# Speed.net
KiCad netlist of a schematic drawn in EAGLE
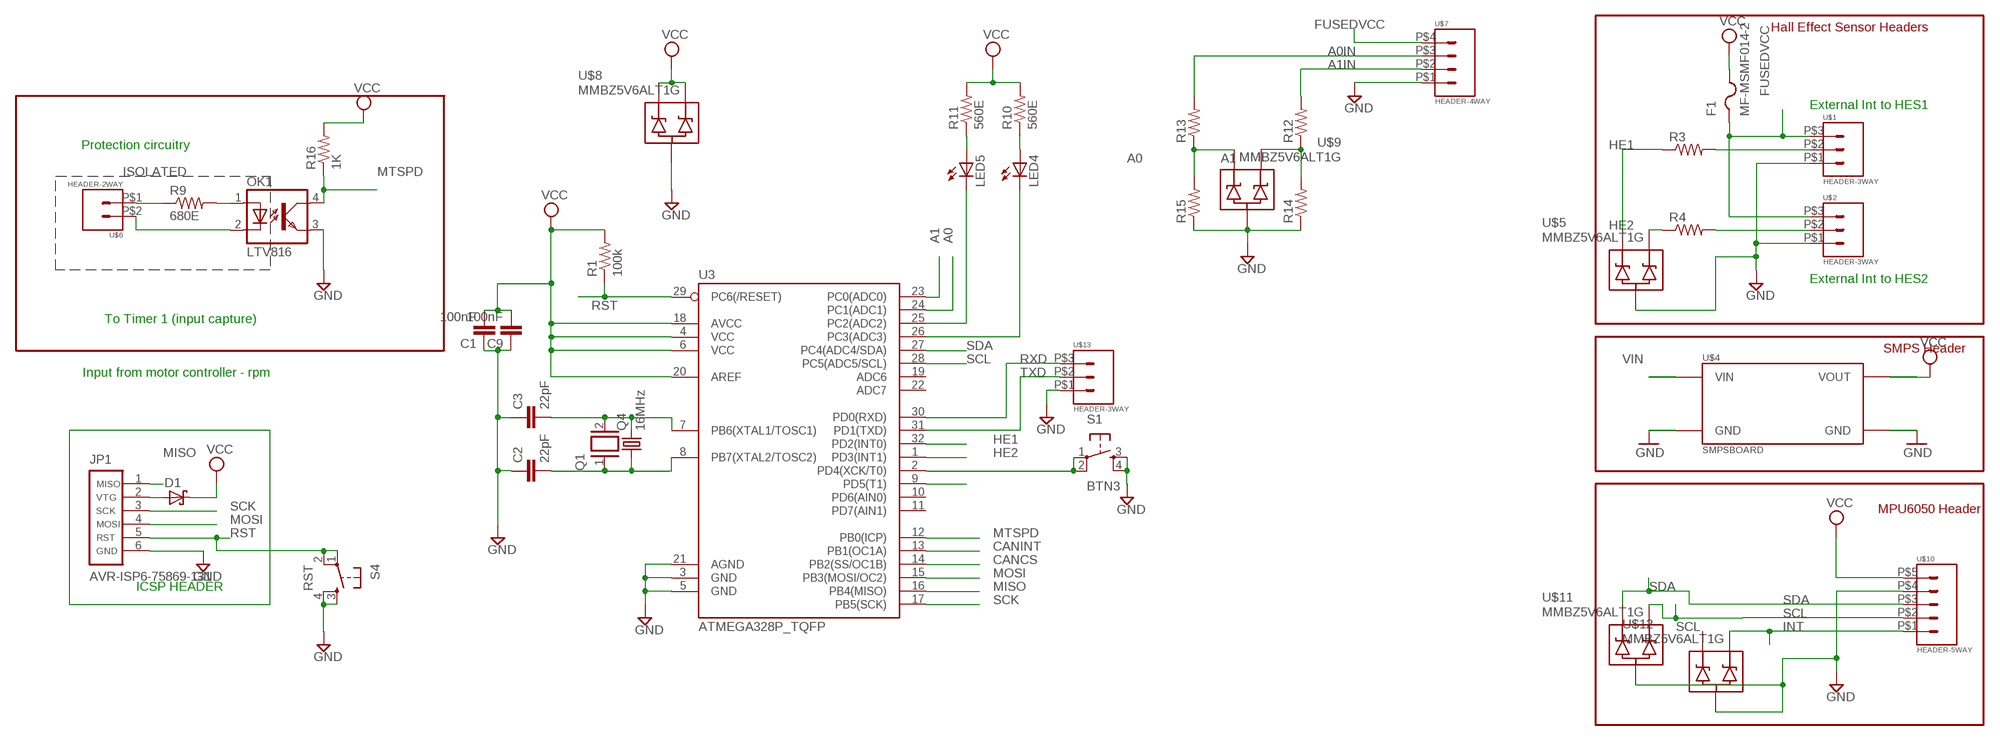
[diagram p0: schematic, sheet 1]
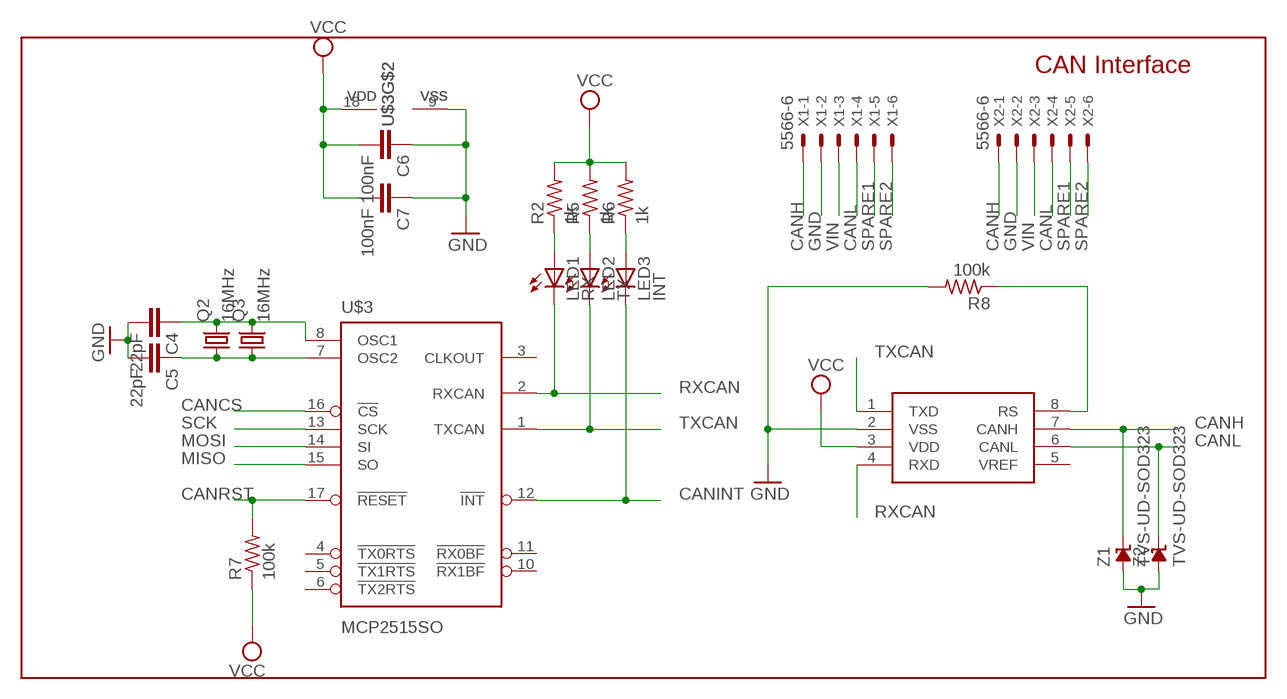
[diagram p1: schematic, sheet 2]

(export (version "E")
  (design (tool "Eeschema 10.0.6"))
  (components
    (comp (ref "C4")
      (value "22pF")
      (footprint "eagle-import:C0805K")
      (libsource (lib "eagle-import") (part "C-EUC0805K"))
    )
    (comp (ref "C5")
      (value "22pF")
      (footprint "eagle-import:C0805K")
      (libsource (lib "eagle-import") (part "C-EUC0805K"))
    )
    (comp (ref "C6")
      (value "100nF")
      (footprint "eagle-import:C0805K")
      (libsource (lib "eagle-import") (part "C-EUC0805K"))
    )
    (comp (ref "C7")
      (value "100nF")
      (footprint "eagle-import:C0805K")
      (libsource (lib "eagle-import") (part "C-EUC0805K"))
    )
    (comp (ref "LED1")
      (value "RX")
      (footprint "eagle-import:CHIP-LED0805")
      (libsource (lib "eagle-import") (part "LEDCHIP-LED0805"))
    )
    (comp (ref "LED2")
      (value "TX")
      (footprint "eagle-import:CHIP-LED0805")
      (libsource (lib "eagle-import") (part "LEDCHIP-LED0805"))
    )
    (comp (ref "LED3")
      (value "INT")
      (footprint "eagle-import:CHIP-LED0805")
      (libsource (lib "eagle-import") (part "LEDCHIP-LED0805"))
    )
    (comp (ref "Q2")
      (value "16MHz")
      (footprint "eagle-import:HC49_S")
      (libsource (lib "eagle-import") (part "CRYSTALHC49S"))
    )
    (comp (ref "Q3")
      (value "16MHz")
      (footprint "eagle-import:HC49UP")
      (libsource (lib "eagle-import") (part "CRYSTALHC49UP"))
    )
    (comp (ref "R2")
      (value "1k")
      (footprint "eagle-import:R0805")
      (libsource (lib "eagle-import") (part "R-US_R0805"))
    )
    (comp (ref "R5")
      (value "1k")
      (footprint "eagle-import:R0805")
      (libsource (lib "eagle-import") (part "R-US_R0805"))
    )
    (comp (ref "R6")
      (value "1k")
      (footprint "eagle-import:R0805")
      (libsource (lib "eagle-import") (part "R-US_R0805"))
    )
    (comp (ref "R7")
      (value "100k")
      (footprint "eagle-import:R0805")
      (libsource (lib "eagle-import") (part "R-US_R0805"))
    )
    (comp (ref "R8")
      (value "100k")
      (footprint "eagle-import:R0805")
      (libsource (lib "eagle-import") (part "R-US_R0805"))
    )
    (comp (ref "U$3")
      (value "MCP2515SO")
      (footprint "eagle-import:SO-18W")
      (libsource (lib "eagle-import") (part "MCP2515SO"))
    )
    (comp (ref "U2")
      (value "MCP2551")
      (footprint "eagle-import:SO08")
      (libsource (lib "eagle-import") (part "MCP2551"))
    )
    (comp (ref "X1")
      (value "5566-6")
      (footprint "eagle-import:5566-6")
      (fields (field (name "MPN") "95566-61002"))
      (libsource (lib "eagle-import") (part "5566-6"))
    )
    (comp (ref "X2")
      (value "5566-6")
      (footprint "eagle-import:5566-6")
      (fields (field (name "MPN") "95566-61002"))
      (libsource (lib "eagle-import") (part "5566-6"))
    )
    (comp (ref "Z1")
      (value "TVS-UD-SOD323")
      (footprint "eagle-import:SOD323")
      (libsource (lib "eagle-import") (part "TVS-UD-SOD323"))
    )
    (comp (ref "Z2")
      (value "TVS-UD-SOD323")
      (footprint "eagle-import:SOD323")
      (libsource (lib "eagle-import") (part "TVS-UD-SOD323"))
    )
    (comp (ref "C1")
      (value "100nF")
      (footprint "eagle-import:C0805")
      (libsource (lib "eagle-import") (part "C-EUC0805"))
    )
    (comp (ref "C2")
      (value "22pF")
      (footprint "eagle-import:C0805")
      (libsource (lib "eagle-import") (part "C-EUC0805"))
    )
    (comp (ref "C3")
      (value "22pF")
      (footprint "eagle-import:C0805")
      (libsource (lib "eagle-import") (part "C-EUC0805"))
    )
    (comp (ref "C9")
      (value "100nF")
      (footprint "eagle-import:C0805")
      (libsource (lib "eagle-import") (part "C-EUC0805"))
    )
    (comp (ref "D1")
      (value "SCHOTTKY-DIODESMD")
      (footprint "eagle-import:SMB")
      (libsource (lib "eagle-import") (part "SCHOTTKY-DIODESMD"))
    )
    (comp (ref "F1")
      (value "MF-MSMF014-2")
      (footprint "eagle-import:1812")
      (libsource (lib "eagle-import") (part "PTCFUSE-1812"))
    )
    (comp (ref "JP1")
      (value "AVR-ISP6-75869-131")
      (footprint "eagle-import:HDR-75869-131")
      (libsource (lib "eagle-import") (part "AVR-ISP6-75869-131"))
    )
    (comp (ref "LED4")
      (value "LEDCHIP-LED0805")
      (footprint "eagle-import:CHIP-LED0805")
      (libsource (lib "eagle-import") (part "LEDCHIP-LED0805"))
    )
    (comp (ref "LED5")
      (value "LEDCHIP-LED0805")
      (footprint "eagle-import:CHIP-LED0805")
      (libsource (lib "eagle-import") (part "LEDCHIP-LED0805"))
    )
    (comp (ref "OK1")
      (value "LTV816")
      (footprint "eagle-import:DIL04")
      (libsource (lib "eagle-import") (part "LTV816"))
    )
    (comp (ref "Q1")
      (value "XTAL/S")
      (footprint "eagle-import:QS")
      (libsource (lib "eagle-import") (part "XTAL/S"))
    )
    (comp (ref "Q4")
      (value "16MHz")
      (footprint "eagle-import:HC49UP")
      (libsource (lib "eagle-import") (part "CRYSTALHC49UP"))
    )
    (comp (ref "R1")
      (value "100k")
      (footprint "eagle-import:M0805")
      (libsource (lib "eagle-import") (part "R-US_M0805"))
    )
    (comp (ref "R3")
      (value "R-US_M0805")
      (footprint "eagle-import:M0805")
      (libsource (lib "eagle-import") (part "R-US_M0805"))
    )
    (comp (ref "R4")
      (value "R-US_M0805")
      (footprint "eagle-import:M0805")
      (libsource (lib "eagle-import") (part "R-US_M0805"))
    )
    (comp (ref "R9")
      (value "680E")
      (footprint "eagle-import:M0805")
      (libsource (lib "eagle-import") (part "R-US_M0805"))
    )
    (comp (ref "R10")
      (value "560E")
      (footprint "eagle-import:M0805")
      (libsource (lib "eagle-import") (part "R-US_M0805"))
    )
    (comp (ref "R11")
      (value "560E")
      (footprint "eagle-import:M0805")
      (libsource (lib "eagle-import") (part "R-US_M0805"))
    )
    (comp (ref "R12")
      (value "R-US_M0805")
      (footprint "eagle-import:M0805")
      (libsource (lib "eagle-import") (part "R-US_M0805"))
    )
    (comp (ref "R13")
      (value "R-US_M0805")
      (footprint "eagle-import:M0805")
      (libsource (lib "eagle-import") (part "R-US_M0805"))
    )
    (comp (ref "R14")
      (value "R-US_M0805")
      (footprint "eagle-import:M0805")
      (libsource (lib "eagle-import") (part "R-US_M0805"))
    )
    (comp (ref "R15")
      (value "R-US_M0805")
      (footprint "eagle-import:M0805")
      (libsource (lib "eagle-import") (part "R-US_M0805"))
    )
    (comp (ref "R16")
      (value "1K")
      (footprint "eagle-import:M0805")
      (libsource (lib "eagle-import") (part "R-US_M0805"))
    )
    (comp (ref "S1")
      (value "BTN3")
      (footprint "eagle-import:TACTILE_SWITCH_SMD")
      (libsource (lib "eagle-import") (part "TAC_SWITCHSMD"))
    )
    (comp (ref "S4")
      (value "RST")
      (footprint "eagle-import:TACTILE_SWITCH_SMD")
      (libsource (lib "eagle-import") (part "TAC_SWITCHSMD"))
    )
    (comp (ref "U$1")
      (value "HEADER-3WAY")
      (footprint "eagle-import:1744426-3")
      (libsource (lib "eagle-import") (part "HEADER-3WAY"))
    )
    (comp (ref "U$2")
      (value "HEADER-3WAY")
      (footprint "eagle-import:1744426-3")
      (libsource (lib "eagle-import") (part "HEADER-3WAY"))
    )
    (comp (ref "U$4")
      (value "SMPSBOARD")
      (footprint "eagle-import:SMPSBOARD")
      (libsource (lib "eagle-import") (part "SMPSBOARD"))
    )
    (comp (ref "U$5")
      (value "MMBZ5V6ALT1G")
      (footprint "eagle-import:SOT23")
      (libsource (lib "eagle-import") (part "MMBZ5V6ALT1G"))
    )
    (comp (ref "U$6")
      (value "HEADER-2WAY")
      (footprint "eagle-import:1744426-2")
      (libsource (lib "eagle-import") (part "HEADER-2WAY"))
    )
    (comp (ref "U$7")
      (value "HEADER-4WAY")
      (footprint "eagle-import:1744426-4")
      (libsource (lib "eagle-import") (part "HEADER-4WAY"))
    )
    (comp (ref "U$8")
      (value "MMBZ5V6ALT1G")
      (footprint "eagle-import:SOT23")
      (libsource (lib "eagle-import") (part "MMBZ5V6ALT1G"))
    )
    (comp (ref "U$9")
      (value "MMBZ5V6ALT1G")
      (footprint "eagle-import:SOT23")
      (libsource (lib "eagle-import") (part "MMBZ5V6ALT1G"))
    )
    (comp (ref "U$10")
      (value "HEADER-5WAY")
      (footprint "eagle-import:1744426-5")
      (libsource (lib "eagle-import") (part "HEADER-5WAY"))
    )
    (comp (ref "U$11")
      (value "MMBZ5V6ALT1G")
      (footprint "eagle-import:SOT23")
      (libsource (lib "eagle-import") (part "MMBZ5V6ALT1G"))
    )
    (comp (ref "U$12")
      (value "MMBZ5V6ALT1G")
      (footprint "eagle-import:SOT23")
      (libsource (lib "eagle-import") (part "MMBZ5V6ALT1G"))
    )
    (comp (ref "U$13")
      (value "HEADER-3WAY")
      (footprint "eagle-import:1744426-3")
      (libsource (lib "eagle-import") (part "HEADER-3WAY"))
    )
    (comp (ref "U3")
      (value "ATMEGA328P_TQFP")
      (footprint "eagle-import:TQFP32-08")
      (libsource (lib "eagle-import") (part "ATMEGA328P_TQFP"))
    )
  )
  (nets
    (net (code "1") (name "A0") (class "Default")
      (node (ref "R12") (pin "1") (pinfunction "1_1") (pintype "passive"))
      (node (ref "R14") (pin "2") (pinfunction "2_2") (pintype "passive"))
      (node (ref "U$9") (pin "2") (pinfunction "A2_2") (pintype "passive"))
      (node (ref "U3") (pin "24") (pinfunction "PC1(ADC1)_24") (pintype "bidirectional"))
    )
    (net (code "2") (name "A0IN") (class "Default")
      (node (ref "R13") (pin "2") (pinfunction "2_2") (pintype "passive"))
      (node (ref "U$7") (pin "P$3") (pinfunction "P$3_P$3") (pintype "passive"))
    )
    (net (code "3") (name "A1") (class "Default")
      (node (ref "R13") (pin "1") (pinfunction "1_1") (pintype "passive"))
      (node (ref "R15") (pin "2") (pinfunction "2_2") (pintype "passive"))
      (node (ref "U$9") (pin "1") (pinfunction "A1_1") (pintype "passive"))
      (node (ref "U3") (pin "23") (pinfunction "PC0(ADC0)_23") (pintype "bidirectional"))
    )
    (net (code "4") (name "A1IN") (class "Default")
      (node (ref "R12") (pin "2") (pinfunction "2_2") (pintype "passive"))
      (node (ref "U$7") (pin "P$2") (pinfunction "P$2_P$2") (pintype "passive"))
    )
    (net (code "5") (name "CANCS") (class "Default")
      (node (ref "U$3") (pin "16") (pinfunction "~{CS}_16") (pintype "input"))
      (node (ref "U3") (pin "14") (pinfunction "PB2(SS/OC1B)_14") (pintype "bidirectional"))
    )
    (net (code "6") (name "CANH") (class "Default")
      (node (ref "U2") (pin "7") (pinfunction "CANH_7") (pintype "bidirectional"))
      (node (ref "X1") (pin "1") (pinfunction "S_1") (pintype "passive"))
      (node (ref "X2") (pin "1") (pinfunction "S_1") (pintype "passive"))
      (node (ref "Z1") (pin "C") (pinfunction "C_C") (pintype "passive"))
    )
    (net (code "7") (name "CANINT") (class "Default")
      (node (ref "LED3") (pin "C") (pinfunction "C_C") (pintype "passive"))
      (node (ref "U$3") (pin "12") (pinfunction "~{INT}_12") (pintype "output"))
      (node (ref "U3") (pin "13") (pinfunction "PB1(OC1A)_13") (pintype "bidirectional"))
    )
    (net (code "8") (name "CANL") (class "Default")
      (node (ref "U2") (pin "6") (pinfunction "CANL_6") (pintype "bidirectional"))
      (node (ref "X1") (pin "4") (pinfunction "S_4") (pintype "passive"))
      (node (ref "X2") (pin "4") (pinfunction "S_4") (pintype "passive"))
      (node (ref "Z2") (pin "C") (pinfunction "C_C") (pintype "passive"))
    )
    (net (code "9") (name "CANRST") (class "Default")
      (node (ref "R7") (pin "2") (pinfunction "2_2") (pintype "passive"))
      (node (ref "U$3") (pin "17") (pinfunction "~{RESET}_17") (pintype "input"))
    )
    (net (code "10") (name "FUSEDVCC") (class "Default")
      (node (ref "F1") (pin "1") (pinfunction "1_1") (pintype "passive"))
      (node (ref "U$1") (pin "P$3") (pinfunction "P$3_P$3") (pintype "passive"))
      (node (ref "U$2") (pin "P$3") (pinfunction "P$3_P$3") (pintype "passive"))
      (node (ref "U$7") (pin "P$4") (pinfunction "P$4_P$4") (pintype "passive"))
    )
    (net (code "11") (name "GND") (class "Default")
      (node (ref "C1") (pin "1") (pinfunction "1_1") (pintype "passive"))
      (node (ref "C2") (pin "1") (pinfunction "1_1") (pintype "passive"))
      (node (ref "C3") (pin "1") (pinfunction "1_1") (pintype "passive"))
      (node (ref "C4") (pin "2") (pinfunction "2_2") (pintype "passive"))
      (node (ref "C5") (pin "2") (pinfunction "2_2") (pintype "passive"))
      (node (ref "C6") (pin "1") (pinfunction "1_1") (pintype "passive"))
      (node (ref "C7") (pin "1") (pinfunction "1_1") (pintype "passive"))
      (node (ref "C9") (pin "1") (pinfunction "1_1") (pintype "passive"))
      (node (ref "JP1") (pin "6") (pinfunction "6_6") (pintype "passive"))
      (node (ref "OK1") (pin "3") (pinfunction "EMIT_3") (pintype "passive"))
      (node (ref "R14") (pin "1") (pinfunction "1_1") (pintype "passive"))
      (node (ref "R15") (pin "1") (pinfunction "1_1") (pintype "passive"))
      (node (ref "R8") (pin "2") (pinfunction "2_2") (pintype "passive"))
      (node (ref "S1") (pin "3") (pinfunction "3_3") (pintype "passive"))
      (node (ref "S1") (pin "4") (pinfunction "4_4") (pintype "passive"))
      (node (ref "S4") (pin "3") (pinfunction "3_3") (pintype "passive"))
      (node (ref "S4") (pin "4") (pinfunction "4_4") (pintype "passive"))
      (node (ref "U$1") (pin "P$1") (pinfunction "P$1_P$1") (pintype "passive"))
      (node (ref "U$10") (pin "P$4") (pinfunction "P$4_P$4") (pintype "passive"))
      (node (ref "U$11") (pin "3") (pinfunction "C_3") (pintype "passive"))
      (node (ref "U$12") (pin "3") (pinfunction "C_3") (pintype "passive"))
      (node (ref "U$13") (pin "P$1") (pinfunction "P$1_P$1") (pintype "passive"))
      (node (ref "U$2") (pin "P$1") (pinfunction "P$1_P$1") (pintype "passive"))
      (node (ref "U$3") (pin "9") (pinfunction "VSS_9") (pintype "power_in"))
      (node (ref "U$4") (pin "GND") (pinfunction "GND_GND") (pintype "bidirectional"))
      (node (ref "U$4") (pin "GND@") (pinfunction "GND_GND@") (pintype "bidirectional"))
      (node (ref "U$5") (pin "3") (pinfunction "C_3") (pintype "passive"))
      (node (ref "U$7") (pin "P$1") (pinfunction "P$1_P$1") (pintype "passive"))
      (node (ref "U$8") (pin "3") (pinfunction "C_3") (pintype "passive"))
      (node (ref "U$9") (pin "3") (pinfunction "C_3") (pintype "passive"))
      (node (ref "U2") (pin "2") (pinfunction "VSS_2") (pintype "bidirectional"))
      (node (ref "U3") (pin "21") (pinfunction "AGND_21") (pintype "bidirectional"))
      (node (ref "U3") (pin "3") (pinfunction "GND_3") (pintype "bidirectional"))
      (node (ref "U3") (pin "5") (pinfunction "GND_5") (pintype "bidirectional"))
      (node (ref "X1") (pin "2") (pinfunction "S_2") (pintype "passive"))
      (node (ref "X2") (pin "2") (pinfunction "S_2") (pintype "passive"))
      (node (ref "Z1") (pin "A") (pinfunction "A_A") (pintype "passive"))
      (node (ref "Z2") (pin "A") (pinfunction "A_A") (pintype "passive"))
    )
    (net (code "12") (name "HE1") (class "Default")
      (node (ref "R3") (pin "1") (pinfunction "1_1") (pintype "passive"))
      (node (ref "U$5") (pin "2") (pinfunction "A2_2") (pintype "passive"))
      (node (ref "U3") (pin "32") (pinfunction "PD2(INT0)_32") (pintype "bidirectional"))
    )
    (net (code "13") (name "HE2") (class "Default")
      (node (ref "R4") (pin "1") (pinfunction "1_1") (pintype "passive"))
      (node (ref "U$5") (pin "1") (pinfunction "A1_1") (pintype "passive"))
      (node (ref "U3") (pin "1") (pinfunction "PD3(INT1)_1") (pintype "bidirectional"))
    )
    (net (code "14") (name "INT") (class "Default")
      (node (ref "U$10") (pin "P$1") (pinfunction "P$1_P$1") (pintype "passive"))
      (node (ref "U$12") (pin "1") (pinfunction "A1_1") (pintype "passive"))
      (node (ref "U3") (pin "9") (pinfunction "PD5(T1)_9") (pintype "bidirectional"))
    )
    (net (code "15") (name "MISO") (class "Default")
      (node (ref "JP1") (pin "1") (pinfunction "1_1") (pintype "passive"))
      (node (ref "U$3") (pin "15") (pinfunction "SO_15") (pintype "output"))
      (node (ref "U3") (pin "16") (pinfunction "PB4(MISO)_16") (pintype "bidirectional"))
    )
    (net (code "16") (name "MOSI") (class "Default")
      (node (ref "JP1") (pin "4") (pinfunction "4_4") (pintype "passive"))
      (node (ref "U$3") (pin "14") (pinfunction "SI_14") (pintype "input"))
      (node (ref "U3") (pin "15") (pinfunction "PB3(MOSI/OC2)_15") (pintype "bidirectional"))
    )
    (net (code "17") (name "MTSPD") (class "Default")
      (node (ref "OK1") (pin "4") (pinfunction "COL_4") (pintype "passive"))
      (node (ref "R16") (pin "1") (pinfunction "1_1") (pintype "passive"))
      (node (ref "U3") (pin "12") (pinfunction "PB0(ICP)_12") (pintype "bidirectional"))
    )
    (net (code "18") (name "Net-(D1-PadA)") (class "Default")
      (node (ref "D1") (pin "A") (pinfunction "A_A") (pintype "passive"))
      (node (ref "JP1") (pin "2") (pinfunction "2_2") (pintype "passive"))
    )
    (net (code "19") (name "Net-(LED1-PadA)") (class "Default")
      (node (ref "LED1") (pin "A") (pinfunction "A_A") (pintype "passive"))
      (node (ref "R2") (pin "1") (pinfunction "1_1") (pintype "passive"))
    )
    (net (code "20") (name "Net-(LED2-PadA)") (class "Default")
      (node (ref "LED2") (pin "A") (pinfunction "A_A") (pintype "passive"))
      (node (ref "R5") (pin "1") (pinfunction "1_1") (pintype "passive"))
    )
    (net (code "21") (name "Net-(LED3-PadA)") (class "Default")
      (node (ref "LED3") (pin "A") (pinfunction "A_A") (pintype "passive"))
      (node (ref "R6") (pin "1") (pinfunction "1_1") (pintype "passive"))
    )
    (net (code "22") (name "Net-(LED4-PadA)") (class "Default")
      (node (ref "LED4") (pin "A") (pinfunction "A_A") (pintype "passive"))
      (node (ref "R10") (pin "1") (pinfunction "1_1") (pintype "passive"))
    )
    (net (code "23") (name "Net-(LED5-PadA)") (class "Default")
      (node (ref "LED5") (pin "A") (pinfunction "A_A") (pintype "passive"))
      (node (ref "R11") (pin "1") (pinfunction "1_1") (pintype "passive"))
    )
    (net (code "24") (name "Net-(OK1-A)") (class "Default")
      (node (ref "OK1") (pin "1") (pinfunction "A_1") (pintype "passive"))
      (node (ref "R9") (pin "2") (pinfunction "2_2") (pintype "passive"))
    )
    (net (code "25") (name "Net-(OK1-C)") (class "Default")
      (node (ref "OK1") (pin "2") (pinfunction "C_2") (pintype "passive"))
      (node (ref "U$6") (pin "P$2") (pinfunction "P$2_P$2") (pintype "passive"))
    )
    (net (code "26") (name "Net-(R3-Pad2)") (class "Default")
      (node (ref "R3") (pin "2") (pinfunction "2_2") (pintype "passive"))
      (node (ref "U$1") (pin "P$2") (pinfunction "P$2_P$2") (pintype "passive"))
    )
    (net (code "27") (name "Net-(R4-Pad2)") (class "Default")
      (node (ref "R4") (pin "2") (pinfunction "2_2") (pintype "passive"))
      (node (ref "U$2") (pin "P$2") (pinfunction "P$2_P$2") (pintype "passive"))
    )
    (net (code "28") (name "Net-(R9-Pad1)") (class "Default")
      (node (ref "R9") (pin "1") (pinfunction "1_1") (pintype "passive"))
      (node (ref "U$6") (pin "P$1") (pinfunction "P$1_P$1") (pintype "passive"))
    )
    (net (code "29") (name "Net-(U$3A-OSC1)") (class "Default")
      (node (ref "C4") (pin "1") (pinfunction "1_1") (pintype "passive"))
      (node (ref "Q2") (pin "2") (pinfunction "2_2") (pintype "passive"))
      (node (ref "Q3") (pin "2") (pinfunction "2_2") (pintype "passive"))
      (node (ref "U$3") (pin "8") (pinfunction "OSC1_8") (pintype "input"))
    )
    (net (code "30") (name "Net-(U$3A-OSC2)") (class "Default")
      (node (ref "C5") (pin "1") (pinfunction "1_1") (pintype "passive"))
      (node (ref "Q2") (pin "1") (pinfunction "1_1") (pintype "passive"))
      (node (ref "Q3") (pin "1") (pinfunction "1_1") (pintype "passive"))
      (node (ref "U$3") (pin "7") (pinfunction "OSC2_7") (pintype "output"))
    )
    (net (code "31") (name "Net-(U2-RS)") (class "Default")
      (node (ref "R8") (pin "1") (pinfunction "1_1") (pintype "passive"))
      (node (ref "U2") (pin "8") (pinfunction "RS_8") (pintype "bidirectional"))
    )
    (net (code "32") (name "Net-(U3-PB6(XTAL1{slash}TOSC1))") (class "Default")
      (node (ref "C3") (pin "2") (pinfunction "2_2") (pintype "passive"))
      (node (ref "Q1") (pin "2") (pinfunction "2_2") (pintype "passive"))
      (node (ref "Q4") (pin "2") (pinfunction "2_2") (pintype "passive"))
      (node (ref "U3") (pin "7") (pinfunction "PB6(XTAL1/TOSC1)_7") (pintype "bidirectional"))
    )
    (net (code "33") (name "Net-(U3-PB7(XTAL2{slash}TOSC2))") (class "Default")
      (node (ref "C2") (pin "2") (pinfunction "2_2") (pintype "passive"))
      (node (ref "Q1") (pin "1") (pinfunction "1_1") (pintype "passive"))
      (node (ref "Q4") (pin "1") (pinfunction "1_1") (pintype "passive"))
      (node (ref "U3") (pin "8") (pinfunction "PB7(XTAL2/TOSC2)_8") (pintype "bidirectional"))
    )
    (net (code "34") (name "Net-(U3-PC2(ADC2))") (class "Default")
      (node (ref "LED5") (pin "C") (pinfunction "C_C") (pintype "passive"))
      (node (ref "U3") (pin "25") (pinfunction "PC2(ADC2)_25") (pintype "bidirectional"))
    )
    (net (code "35") (name "Net-(U3-PC3(ADC3))") (class "Default")
      (node (ref "LED4") (pin "C") (pinfunction "C_C") (pintype "passive"))
      (node (ref "U3") (pin "26") (pinfunction "PC3(ADC3)_26") (pintype "bidirectional"))
    )
    (net (code "36") (name "Net-(U3-PD4(XCK{slash}T0))") (class "Default")
      (node (ref "S1") (pin "1") (pinfunction "1_1") (pintype "passive"))
      (node (ref "S1") (pin "2") (pinfunction "2_2") (pintype "passive"))
      (node (ref "U3") (pin "2") (pinfunction "PD4(XCK/T0)_2") (pintype "bidirectional"))
    )
    (net (code "37") (name "RST") (class "Default")
      (node (ref "JP1") (pin "5") (pinfunction "5_5") (pintype "passive"))
      (node (ref "R1") (pin "1") (pinfunction "1_1") (pintype "passive"))
      (node (ref "S4") (pin "1") (pinfunction "1_1") (pintype "passive"))
      (node (ref "S4") (pin "2") (pinfunction "2_2") (pintype "passive"))
      (node (ref "U3") (pin "29") (pinfunction "PC6(/RESET)_29") (pintype "bidirectional"))
    )
    (net (code "38") (name "RXCAN") (class "Default")
      (node (ref "LED1") (pin "C") (pinfunction "C_C") (pintype "passive"))
      (node (ref "U$3") (pin "2") (pinfunction "RXCAN_2") (pintype "input"))
      (node (ref "U2") (pin "4") (pinfunction "RXD_4") (pintype "bidirectional"))
    )
    (net (code "39") (name "RXD") (class "Default")
      (node (ref "U$13") (pin "P$3") (pinfunction "P$3_P$3") (pintype "passive"))
      (node (ref "U3") (pin "30") (pinfunction "PD0(RXD)_30") (pintype "bidirectional"))
    )
    (net (code "40") (name "SCK") (class "Default")
      (node (ref "JP1") (pin "3") (pinfunction "3_3") (pintype "passive"))
      (node (ref "U$3") (pin "13") (pinfunction "SCK_13") (pintype "input"))
      (node (ref "U3") (pin "17") (pinfunction "PB5(SCK)_17") (pintype "bidirectional"))
    )
    (net (code "41") (name "SCL") (class "Default")
      (node (ref "U$10") (pin "P$2") (pinfunction "P$2_P$2") (pintype "passive"))
      (node (ref "U$11") (pin "1") (pinfunction "A1_1") (pintype "passive"))
      (node (ref "U3") (pin "28") (pinfunction "PC5(ADC5/SCL)_28") (pintype "bidirectional"))
    )
    (net (code "42") (name "SDA") (class "Default")
      (node (ref "U$10") (pin "P$3") (pinfunction "P$3_P$3") (pintype "passive"))
      (node (ref "U$11") (pin "2") (pinfunction "A2_2") (pintype "passive"))
      (node (ref "U3") (pin "27") (pinfunction "PC4(ADC4/SDA)_27") (pintype "bidirectional"))
    )
    (net (code "43") (name "SPARE1") (class "Default")
      (node (ref "X1") (pin "5") (pinfunction "S_5") (pintype "passive"))
      (node (ref "X2") (pin "5") (pinfunction "S_5") (pintype "passive"))
    )
    (net (code "44") (name "SPARE2") (class "Default")
      (node (ref "X1") (pin "6") (pinfunction "S_6") (pintype "passive"))
      (node (ref "X2") (pin "6") (pinfunction "S_6") (pintype "passive"))
    )
    (net (code "45") (name "TXCAN") (class "Default")
      (node (ref "LED2") (pin "C") (pinfunction "C_C") (pintype "passive"))
      (node (ref "U$3") (pin "1") (pinfunction "TXCAN_1") (pintype "output"))
      (node (ref "U2") (pin "1") (pinfunction "TXD_1") (pintype "bidirectional"))
    )
    (net (code "46") (name "TXD") (class "Default")
      (node (ref "U$13") (pin "P$2") (pinfunction "P$2_P$2") (pintype "passive"))
      (node (ref "U3") (pin "31") (pinfunction "PD1(TXD)_31") (pintype "bidirectional"))
    )
    (net (code "47") (name "VCC") (class "Default")
      (node (ref "C1") (pin "2") (pinfunction "2_2") (pintype "passive"))
      (node (ref "C6") (pin "2") (pinfunction "2_2") (pintype "passive"))
      (node (ref "C7") (pin "2") (pinfunction "2_2") (pintype "passive"))
      (node (ref "C9") (pin "2") (pinfunction "2_2") (pintype "passive"))
      (node (ref "D1") (pin "C") (pinfunction "C_C") (pintype "passive"))
      (node (ref "F1") (pin "2") (pinfunction "2_2") (pintype "passive"))
      (node (ref "R1") (pin "2") (pinfunction "2_2") (pintype "passive"))
      (node (ref "R10") (pin "2") (pinfunction "2_2") (pintype "passive"))
      (node (ref "R11") (pin "2") (pinfunction "2_2") (pintype "passive"))
      (node (ref "R16") (pin "2") (pinfunction "2_2") (pintype "passive"))
      (node (ref "R2") (pin "2") (pinfunction "2_2") (pintype "passive"))
      (node (ref "R5") (pin "2") (pinfunction "2_2") (pintype "passive"))
      (node (ref "R6") (pin "2") (pinfunction "2_2") (pintype "passive"))
      (node (ref "R7") (pin "1") (pinfunction "1_1") (pintype "passive"))
      (node (ref "U$10") (pin "P$5") (pinfunction "P$5_P$5") (pintype "passive"))
      (node (ref "U$3") (pin "18") (pinfunction "VDD_18") (pintype "power_in"))
      (node (ref "U$4") (pin "VOUT") (pinfunction "VOUT_VOUT") (pintype "bidirectional"))
      (node (ref "U$8") (pin "1") (pinfunction "A1_1") (pintype "passive"))
      (node (ref "U$8") (pin "2") (pinfunction "A2_2") (pintype "passive"))
      (node (ref "U2") (pin "3") (pinfunction "VDD_3") (pintype "bidirectional"))
      (node (ref "U3") (pin "18") (pinfunction "AVCC_18") (pintype "bidirectional"))
      (node (ref "U3") (pin "20") (pinfunction "AREF_20") (pintype "bidirectional"))
      (node (ref "U3") (pin "4") (pinfunction "VCC_4") (pintype "bidirectional"))
      (node (ref "U3") (pin "6") (pinfunction "VCC_6") (pintype "bidirectional"))
    )
    (net (code "48") (name "VIN") (class "Default")
      (node (ref "U$4") (pin "VIN") (pinfunction "VIN_VIN") (pintype "bidirectional"))
      (node (ref "X1") (pin "3") (pinfunction "S_3") (pintype "passive"))
      (node (ref "X2") (pin "3") (pinfunction "S_3") (pintype "passive"))
    )
    (net (code "49") (name "unconnected-(U$3A-CLKOUT-Pad3)") (class "Default")
      (node (ref "U$3") (pin "3") (pinfunction "CLKOUT_3") (pintype "output"))
    )
    (net (code "50") (name "unconnected-(U$3A-~{RX0BF}-Pad11)") (class "Default")
      (node (ref "U$3") (pin "11") (pinfunction "~{RX0BF}_11") (pintype "output"))
    )
    (net (code "51") (name "unconnected-(U$3A-~{RX1BF}-Pad10)") (class "Default")
      (node (ref "U$3") (pin "10") (pinfunction "~{RX1BF}_10") (pintype "output"))
    )
    (net (code "52") (name "unconnected-(U$3A-~{TX0RTS}-Pad4)") (class "Default")
      (node (ref "U$3") (pin "4") (pinfunction "~{TX0RTS}_4") (pintype "input"))
    )
    (net (code "53") (name "unconnected-(U$3A-~{TX1RTS}-Pad5)") (class "Default")
      (node (ref "U$3") (pin "5") (pinfunction "~{TX1RTS}_5") (pintype "input"))
    )
    (net (code "54") (name "unconnected-(U$3A-~{TX2RTS}-Pad6)") (class "Default")
      (node (ref "U$3") (pin "6") (pinfunction "~{TX2RTS}_6") (pintype "input"))
    )
    (net (code "55") (name "unconnected-(U$12-A2-Pad2)") (class "Default")
      (node (ref "U$12") (pin "2") (pinfunction "A2_2") (pintype "passive"))
    )
    (net (code "56") (name "unconnected-(U2-VREF-Pad5)") (class "Default")
      (node (ref "U2") (pin "5") (pinfunction "VREF_5") (pintype "bidirectional"))
    )
    (net (code "57") (name "unconnected-(U3-ADC6-Pad19)") (class "Default")
      (node (ref "U3") (pin "19") (pinfunction "ADC6_19") (pintype "bidirectional"))
    )
    (net (code "58") (name "unconnected-(U3-ADC7-Pad22)") (class "Default")
      (node (ref "U3") (pin "22") (pinfunction "ADC7_22") (pintype "bidirectional"))
    )
    (net (code "59") (name "unconnected-(U3-PD6(AIN0)-Pad10)") (class "Default")
      (node (ref "U3") (pin "10") (pinfunction "PD6(AIN0)_10") (pintype "bidirectional"))
    )
    (net (code "60") (name "unconnected-(U3-PD7(AIN1)-Pad11)") (class "Default")
      (node (ref "U3") (pin "11") (pinfunction "PD7(AIN1)_11") (pintype "bidirectional"))
    )
  )
)
